# buck_boost_converter.net
KiCad netlist of a schematic drawn in Altium Designer
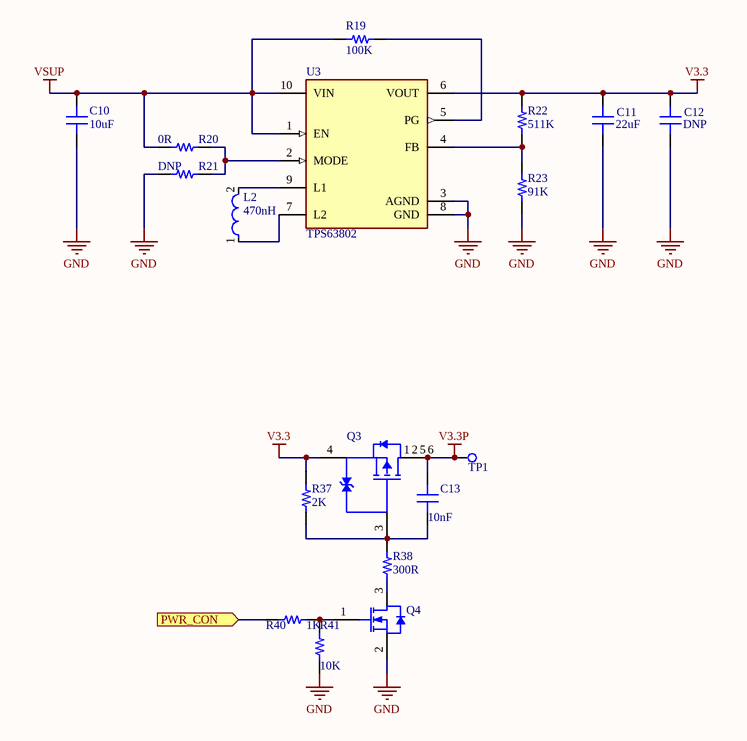
[diagram p0: buck_boost_converter.SchDoc]

(export (version "E")
  (design (tool "Eeschema 10.0.6"))
  (components
    (comp (ref "C10")
      (value "10uF")
      (footprint "CAP 0603_1608")
      (description "SMT Capacitor")
      (fields (field (name "MF") "Murata") (field (name "MP") "GRM188R61C106MAALD"))
      (libsource (lib "Capacitor") (part "Capacitor"))
    )
    (comp (ref "C11")
      (value "22uF")
      (footprint "CAP 0603_1608")
      (description "SMT Capacitor")
      (fields (field (name "MF") "Murata") (field (name "MP") "GRM188R61A226ME15D"))
      (libsource (lib "Capacitor") (part "Capacitor"))
    )
    (comp (ref "C12")
      (value "DNP")
      (footprint "CAP 0603_1608")
      (description "SMT Capacitor")
      (fields (field (name "MF") "Murata") (field (name "MP") "GRM188R61A226ME15D"))
      (libsource (lib "Capacitor") (part "Capacitor"))
    )
    (comp (ref "C13")
      (value "10nF")
      (footprint "CAP 0603_1608")
      (description "SMT Capacitor")
      (fields (field (name "MF") "Murata") (field (name "MP") "GRM1885C1E103JA01D"))
      (libsource (lib "Capacitor") (part "Capacitor"))
    )
    (comp (ref "L2")
      (value "470nH")
      (footprint "Coilcraft_XFL4015_MFG")
      (description "Fixed Inductors 2.2uH 20% High Temp AEC-Q200")
      (fields (field (name "MF") "Coilcraft") (field (name "MP") "XFL4015-471MEC"))
      (libsource (lib "Inductor") (part "Inductor_sm"))
    )
    (comp (ref "Q3")
      (value "P Mosfet")
      (footprint "Diodes_Inc._TSOT26_MFG")
      (description "P-Channel Enhancement Mode MOS Transistor, 3-Pin SOT23")
      (fields (field (name "MF") "Vishay") (field (name "MP") "SI3421DV-T1-GE3"))
      (libsource (lib "Mosfet") (part "Mosfet-P-6_ESD"))
    )
    (comp (ref "Q4")
      (value "N Mosfet")
      (footprint "ON SEMI SOT-23-3")
      (description "N-Channel Enhancement Mode MOS Transistor, 30 V, 0.85 A, 3-Pin SOT23, Tape and Reel")
      (fields (field (name "MF") "Diodes") (field (name "MP") "DMN2053U-7"))
      (libsource (lib "Mosfet") (part "Mosfet-N"))
    )
    (comp (ref "R19")
      (value "100K")
      (footprint "RES 0603_1608")
      (description "SMT Resistor")
      (fields (field (name "MF") "YAGEO") (field (name "MP") "AC0603FR-07100KL"))
      (libsource (lib "Resistor") (part "Resistor"))
    )
    (comp (ref "R20")
      (value "0R")
      (footprint "RES 0603_1608")
      (description "SMT Resistor")
      (fields (field (name "MF") "YAGEO") (field (name "MP") "AC0603FR-070RL"))
      (libsource (lib "Resistor") (part "Resistor"))
    )
    (comp (ref "R21")
      (value "DNP")
      (footprint "RES 0603_1608")
      (description "SMT Resistor")
      (fields (field (name "MF") "YAGEO") (field (name "MP") "AC0603FR-070RL"))
      (libsource (lib "Resistor") (part "Resistor"))
    )
    (comp (ref "R22")
      (value "511K")
      (footprint "RES 0603_1608")
      (description "SMT Resistor")
      (fields (field (name "MF") "YAGEO") (field (name "MP") "AC0603FR-07511KL"))
      (libsource (lib "Resistor") (part "Resistor"))
    )
    (comp (ref "R23")
      (value "91K")
      (footprint "RES 0603_1608")
      (description "SMT Resistor")
      (fields (field (name "MF") "YAGEO") (field (name "MP") "AC0603FR-0791KL"))
      (libsource (lib "Resistor") (part "Resistor"))
    )
    (comp (ref "R37")
      (value "2K")
      (footprint "RES 0603_1608")
      (description "SMT Resistor")
      (fields (field (name "MF") "YAGEO") (field (name "MP") "AC0603FR-072KL"))
      (libsource (lib "Resistor") (part "Resistor"))
    )
    (comp (ref "R38")
      (value "300R")
      (footprint "RES 0603_1608")
      (description "SMT Resistor")
      (fields (field (name "MF") "YAGEO") (field (name "MP") "AC0603FR-07300RL"))
      (libsource (lib "Resistor") (part "Resistor"))
    )
    (comp (ref "R40")
      (value "1K")
      (footprint "RES 0603_1608")
      (description "SMT Resistor")
      (fields (field (name "MF") "YAGEO") (field (name "MP") "AC0603FR-071KL"))
      (libsource (lib "Resistor") (part "Resistor"))
    )
    (comp (ref "R41")
      (value "10K")
      (footprint "RES 0603_1608")
      (description "SMT Resistor")
      (fields (field (name "MF") "YAGEO") (field (name "MP") "AC0603FR-0710KL"))
      (libsource (lib "Resistor") (part "Resistor"))
    )
    (comp (ref "TP1")
      (value "Test Point")
      (footprint "TPSMD_S1")
      (libsource (lib "Passive") (part "Test Point"))
    )
    (comp (ref "U3")
      (value "TPS63802")
      (footprint "Texas_Instruments_DLA0010A_MFG")
      (fields (field (name "MF") "Texas Instruments") (field (name "MP") "TPS63802DLAT"))
      (libsource (lib "SwitchingRegulators") (part "TPS63802"))
    )
  )
  (nets
    (net (code "1") (name "/PWR_CON") (class "Default")
      (node (ref "R40") (pin "1") (pinfunction "1_1") (pintype "passive"))
    )
    (net (code "2") (name "GND") (class "Default")
      (node (ref "C10") (pin "2") (pinfunction "2_2") (pintype "passive"))
      (node (ref "C11") (pin "2") (pinfunction "2_2") (pintype "passive"))
      (node (ref "C12") (pin "2") (pinfunction "2_2") (pintype "passive"))
      (node (ref "Q4") (pin "2") (pinfunction "S_2") (pintype "passive"))
      (node (ref "R21") (pin "1") (pinfunction "1_1") (pintype "passive"))
      (node (ref "R23") (pin "2") (pinfunction "2_2") (pintype "passive"))
      (node (ref "R41") (pin "1") (pinfunction "1_1") (pintype "passive"))
      (node (ref "U3") (pin "3") (pinfunction "AGND_3") (pintype "power_in"))
      (node (ref "U3") (pin "8") (pinfunction "GND_8") (pintype "power_in"))
    )
    (net (code "3") (name "Net-(Q3-G)") (class "Default")
      (node (ref "C13") (pin "2") (pinfunction "2_2") (pintype "passive"))
      (node (ref "Q3") (pin "3") (pinfunction "G_3") (pintype "passive"))
      (node (ref "R37") (pin "2") (pinfunction "2_2") (pintype "passive"))
      (node (ref "R38") (pin "2") (pinfunction "2_2") (pintype "passive"))
    )
    (net (code "4") (name "Net-(Q4-D)") (class "Default")
      (node (ref "Q4") (pin "3") (pinfunction "D_3") (pintype "passive"))
      (node (ref "R38") (pin "1") (pinfunction "1_1") (pintype "passive"))
    )
    (net (code "5") (name "Net-(Q4-G)") (class "Default")
      (node (ref "Q4") (pin "1") (pinfunction "G_1") (pintype "passive"))
      (node (ref "R40") (pin "2") (pinfunction "2_2") (pintype "passive"))
      (node (ref "R41") (pin "2") (pinfunction "2_2") (pintype "passive"))
    )
    (net (code "6") (name "Net-(U3-FB)") (class "Default")
      (node (ref "R22") (pin "2") (pinfunction "2_2") (pintype "passive"))
      (node (ref "R23") (pin "1") (pinfunction "1_1") (pintype "passive"))
      (node (ref "U3") (pin "4") (pinfunction "FB_4") (pintype "passive"))
    )
    (net (code "7") (name "Net-(U3-L1)") (class "Default")
      (node (ref "L2") (pin "2") (pinfunction "2_2") (pintype "passive"))
      (node (ref "U3") (pin "9") (pinfunction "L1_9") (pintype "passive"))
    )
    (net (code "8") (name "Net-(U3-L2)") (class "Default")
      (node (ref "L2") (pin "1") (pinfunction "1_1") (pintype "passive"))
      (node (ref "U3") (pin "7") (pinfunction "L2_7") (pintype "passive"))
    )
    (net (code "9") (name "Net-(U3-MODE)") (class "Default")
      (node (ref "R20") (pin "2") (pinfunction "2_2") (pintype "passive"))
      (node (ref "R21") (pin "2") (pinfunction "2_2") (pintype "passive"))
      (node (ref "U3") (pin "2") (pinfunction "MODE_2") (pintype "input"))
    )
    (net (code "10") (name "Net-(U3-PG)") (class "Default")
      (node (ref "R19") (pin "2") (pinfunction "2_2") (pintype "passive"))
      (node (ref "U3") (pin "5") (pinfunction "PG_5") (pintype "output"))
    )
    (net (code "11") (name "V3.3") (class "Default")
      (node (ref "C11") (pin "1") (pinfunction "1_1") (pintype "passive"))
      (node (ref "C12") (pin "1") (pinfunction "1_1") (pintype "passive"))
      (node (ref "Q3") (pin "4") (pinfunction "S_4") (pintype "passive"))
      (node (ref "R22") (pin "1") (pinfunction "1_1") (pintype "passive"))
      (node (ref "R37") (pin "1") (pinfunction "1_1") (pintype "passive"))
      (node (ref "U3") (pin "6") (pinfunction "VOUT_6") (pintype "power_in"))
    )
    (net (code "12") (name "V3.3P") (class "Default")
      (node (ref "C13") (pin "1") (pinfunction "1_1") (pintype "passive"))
      (node (ref "Q3") (pin "1") (pinfunction "D_1") (pintype "passive"))
      (node (ref "Q3") (pin "2") (pinfunction "D_2") (pintype "passive"))
      (node (ref "Q3") (pin "5") (pinfunction "D_5") (pintype "passive"))
      (node (ref "Q3") (pin "6") (pinfunction "D_6") (pintype "passive"))
      (node (ref "TP1") (pin "1") (pinfunction "TP_1") (pintype "passive"))
    )
    (net (code "13") (name "VSUP") (class "Default")
      (node (ref "C10") (pin "1") (pinfunction "1_1") (pintype "passive"))
      (node (ref "R19") (pin "1") (pinfunction "1_1") (pintype "passive"))
      (node (ref "R20") (pin "1") (pinfunction "1_1") (pintype "passive"))
      (node (ref "U3") (pin "1") (pinfunction "EN_1") (pintype "input"))
      (node (ref "U3") (pin "10") (pinfunction "VIN_10") (pintype "power_in"))
    )
  )
)
